# sd_tos_dip28.net
KiCad netlist of a schematic drawn in EAGLE
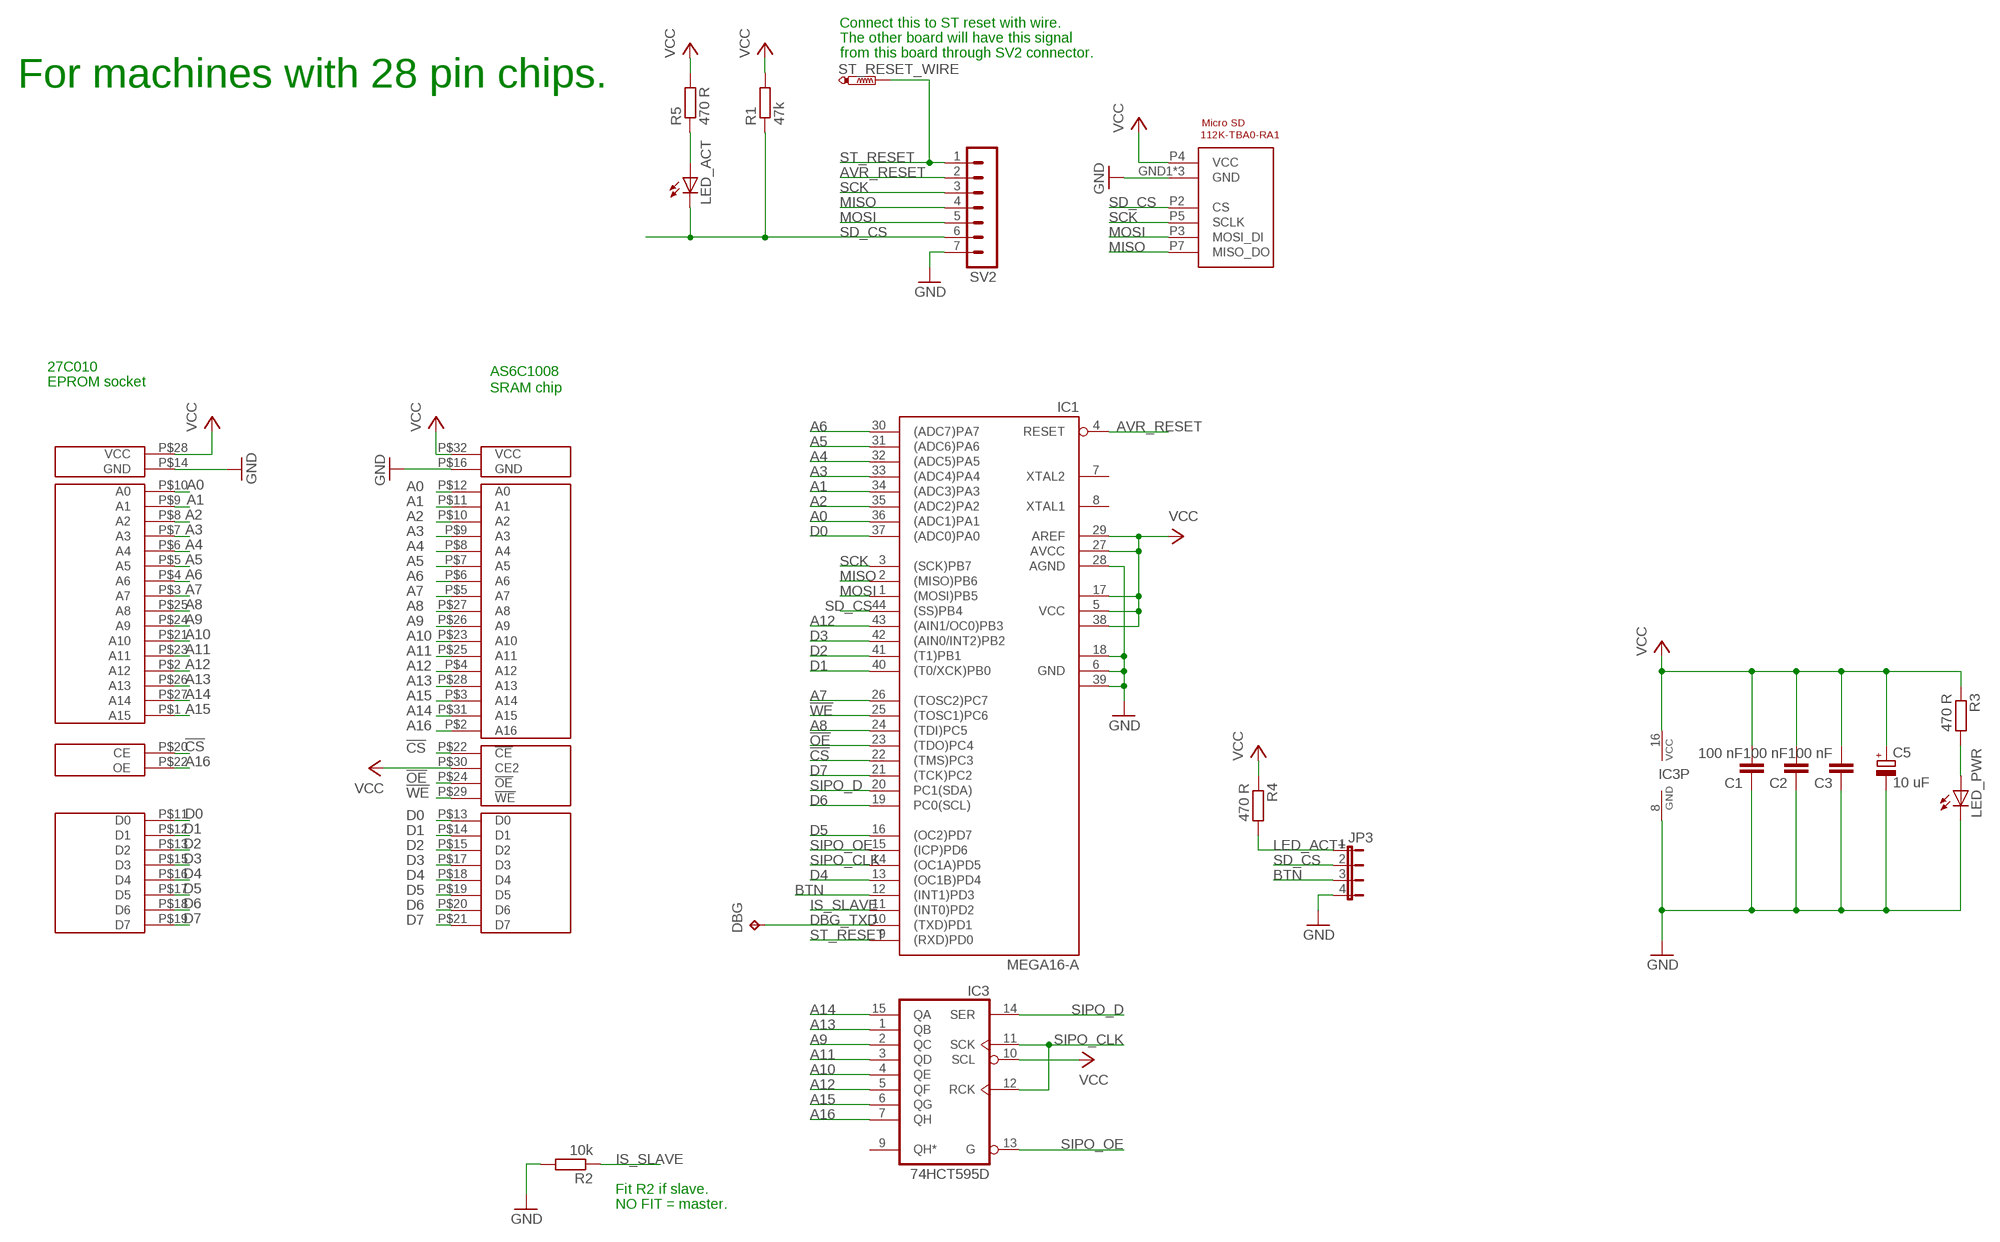
[diagram p0: schematic, sheet 1]

(export (version "E")
  (design (tool "Eeschema 10.0.6"))
  (components
    (comp (ref "C1")
      (value "100 nF")
      (footprint "eagle-import:C0603")
      (libsource (lib "eagle-import") (part "C-EUC0603"))
    )
    (comp (ref "C2")
      (value "100 nF")
      (footprint "eagle-import:C0603")
      (libsource (lib "eagle-import") (part "C-EUC0603"))
    )
    (comp (ref "C3")
      (value "100 nF")
      (footprint "eagle-import:C0603")
      (libsource (lib "eagle-import") (part "C-EUC0603"))
    )
    (comp (ref "C5")
      (value "10 uF")
      (footprint "eagle-import:SANYO-OSCON_SMD_B6")
      (libsource (lib "eagle-import") (part "CPOL-EUSANYO_SMD_B6"))
    )
    (comp (ref "DBG")
      (value "TPB1,27")
      (footprint "eagle-import:B1,27")
      (libsource (lib "eagle-import") (part "TPB1,27"))
    )
    (comp (ref "IC1")
      (value "MEGA16-A")
      (footprint "eagle-import:TQFP44")
      (libsource (lib "eagle-import") (part "MEGA16-A"))
    )
    (comp (ref "IC3")
      (value "74HCT595D")
      (footprint "eagle-import:SO16")
      (libsource (lib "eagle-import") (part "74595DHCT"))
    )
    (comp (ref "JP3")
      (value "JP4E")
      (footprint "eagle-import:JP4")
      (libsource (lib "eagle-import") (part "JP4E"))
    )
    (comp (ref "LED_ACT")
      (value "LEDCHIP-LED0805")
      (footprint "eagle-import:CHIP-LED0805")
      (libsource (lib "eagle-import") (part "LEDCHIP-LED0805"))
    )
    (comp (ref "LED_PWR")
      (value "LEDCHIP-LED0805")
      (footprint "eagle-import:CHIP-LED0805")
      (libsource (lib "eagle-import") (part "LEDCHIP-LED0805"))
    )
    (comp (ref "R1")
      (value "47k")
      (footprint "eagle-import:R0603")
      (libsource (lib "eagle-import") (part "R-EU_R0603"))
    )
    (comp (ref "R2")
      (value "10k")
      (footprint "eagle-import:R0603")
      (libsource (lib "eagle-import") (part "R-EU_R0603"))
    )
    (comp (ref "R3")
      (value "470 R")
      (footprint "eagle-import:R0603")
      (libsource (lib "eagle-import") (part "R-EU_R0603"))
    )
    (comp (ref "R4")
      (value "470 R")
      (footprint "eagle-import:R0603")
      (libsource (lib "eagle-import") (part "R-EU_R0603"))
    )
    (comp (ref "R5")
      (value "470 R")
      (footprint "eagle-import:R0603")
      (libsource (lib "eagle-import") (part "R-EU_R0603"))
    )
    (comp (ref "ST_RESET_WIRE")
      (value "PTR1PAD1-13")
      (footprint "eagle-import:P1-13")
      (libsource (lib "eagle-import") (part "PTR1PAD1-13"))
    )
    (comp (ref "SV2")
      (value "MA07-1")
      (footprint "eagle-import:MA07-1")
      (libsource (lib "eagle-import") (part "MA07-1"))
    )
    (comp (ref "U$1")
      (value "27C256BOTTOM_ONLY")
      (footprint "eagle-import:DIP28_BOTTOM_ONLY")
      (libsource (lib "eagle-import") (part "27C256BOTTOM_ONLY"))
    )
    (comp (ref "U$2")
      (value "AS6C1008DIP32")
      (footprint "eagle-import:DIP32")
      (libsource (lib "eagle-import") (part "AS6C1008DIP32"))
    )
    (comp (ref "U$3")
      (value "MICRO_SD")
      (footprint "eagle-import:MICRO_SD")
      (libsource (lib "eagle-import") (part "MICRO_SD"))
    )
  )
  (nets
    (net (code "1") (name "/A0") (class "Default")
      (node (ref "IC1") (pin "36") (pinfunction "(ADC1)PA1_36") (pintype "bidirectional"))
      (node (ref "U$1") (pin "P$10") (pinfunction "A0_P$10") (pintype "bidirectional"))
      (node (ref "U$2") (pin "P$12") (pinfunction "A0_P$12") (pintype "bidirectional"))
    )
    (net (code "2") (name "/A1") (class "Default")
      (node (ref "IC1") (pin "34") (pinfunction "(ADC3)PA3_34") (pintype "bidirectional"))
      (node (ref "U$1") (pin "P$9") (pinfunction "A1_P$9") (pintype "bidirectional"))
      (node (ref "U$2") (pin "P$11") (pinfunction "A1_P$11") (pintype "bidirectional"))
    )
    (net (code "3") (name "/A2") (class "Default")
      (node (ref "IC1") (pin "35") (pinfunction "(ADC2)PA2_35") (pintype "bidirectional"))
      (node (ref "U$1") (pin "P$8") (pinfunction "A2_P$8") (pintype "bidirectional"))
      (node (ref "U$2") (pin "P$10") (pinfunction "A2_P$10") (pintype "bidirectional"))
    )
    (net (code "4") (name "/A3") (class "Default")
      (node (ref "IC1") (pin "33") (pinfunction "(ADC4)PA4_33") (pintype "bidirectional"))
      (node (ref "U$1") (pin "P$7") (pinfunction "A3_P$7") (pintype "bidirectional"))
      (node (ref "U$2") (pin "P$9") (pinfunction "A3_P$9") (pintype "bidirectional"))
    )
    (net (code "5") (name "/A4") (class "Default")
      (node (ref "IC1") (pin "32") (pinfunction "(ADC5)PA5_32") (pintype "bidirectional"))
      (node (ref "U$1") (pin "P$6") (pinfunction "A4_P$6") (pintype "bidirectional"))
      (node (ref "U$2") (pin "P$8") (pinfunction "A4_P$8") (pintype "bidirectional"))
    )
    (net (code "6") (name "/A5") (class "Default")
      (node (ref "IC1") (pin "31") (pinfunction "(ADC6)PA6_31") (pintype "bidirectional"))
      (node (ref "U$1") (pin "P$5") (pinfunction "A5_P$5") (pintype "bidirectional"))
      (node (ref "U$2") (pin "P$7") (pinfunction "A5_P$7") (pintype "bidirectional"))
    )
    (net (code "7") (name "/A6") (class "Default")
      (node (ref "IC1") (pin "30") (pinfunction "(ADC7)PA7_30") (pintype "bidirectional"))
      (node (ref "U$1") (pin "P$4") (pinfunction "A6_P$4") (pintype "bidirectional"))
      (node (ref "U$2") (pin "P$6") (pinfunction "A6_P$6") (pintype "bidirectional"))
    )
    (net (code "8") (name "/A7") (class "Default")
      (node (ref "IC1") (pin "26") (pinfunction "(TOSC2)PC7_26") (pintype "bidirectional"))
      (node (ref "U$1") (pin "P$3") (pinfunction "A7_P$3") (pintype "bidirectional"))
      (node (ref "U$2") (pin "P$5") (pinfunction "A7_P$5") (pintype "bidirectional"))
    )
    (net (code "9") (name "/A8") (class "Default")
      (node (ref "IC1") (pin "24") (pinfunction "(TDI)PC5_24") (pintype "bidirectional"))
      (node (ref "U$1") (pin "P$25") (pinfunction "A8_P$25") (pintype "bidirectional"))
      (node (ref "U$2") (pin "P$27") (pinfunction "A8_P$27") (pintype "bidirectional"))
    )
    (net (code "10") (name "/A9") (class "Default")
      (node (ref "IC3") (pin "2") (pinfunction "QC_2") (pintype "tri_state"))
      (node (ref "U$1") (pin "P$24") (pinfunction "A9_P$24") (pintype "bidirectional"))
      (node (ref "U$2") (pin "P$26") (pinfunction "A9_P$26") (pintype "bidirectional"))
    )
    (net (code "11") (name "/A10") (class "Default")
      (node (ref "IC3") (pin "4") (pinfunction "QE_4") (pintype "tri_state"))
      (node (ref "U$1") (pin "P$21") (pinfunction "A10_P$21") (pintype "bidirectional"))
      (node (ref "U$2") (pin "P$23") (pinfunction "A10_P$23") (pintype "bidirectional"))
    )
    (net (code "12") (name "/A11") (class "Default")
      (node (ref "IC3") (pin "3") (pinfunction "QD_3") (pintype "tri_state"))
      (node (ref "U$1") (pin "P$23") (pinfunction "A11_P$23") (pintype "bidirectional"))
      (node (ref "U$2") (pin "P$25") (pinfunction "A11_P$25") (pintype "bidirectional"))
    )
    (net (code "13") (name "/A12") (class "Default")
      (node (ref "IC1") (pin "43") (pinfunction "(AIN1/OC0)PB3_43") (pintype "bidirectional"))
      (node (ref "IC3") (pin "5") (pinfunction "QF_5") (pintype "tri_state"))
      (node (ref "U$1") (pin "P$2") (pinfunction "A12_P$2") (pintype "bidirectional"))
      (node (ref "U$2") (pin "P$4") (pinfunction "A12_P$4") (pintype "bidirectional"))
    )
    (net (code "14") (name "/A13") (class "Default")
      (node (ref "IC3") (pin "1") (pinfunction "QB_1") (pintype "tri_state"))
      (node (ref "U$1") (pin "P$26") (pinfunction "A13_P$26") (pintype "bidirectional"))
      (node (ref "U$2") (pin "P$28") (pinfunction "A13_P$28") (pintype "bidirectional"))
    )
    (net (code "15") (name "/A14") (class "Default")
      (node (ref "IC3") (pin "15") (pinfunction "QA_15") (pintype "tri_state"))
      (node (ref "U$1") (pin "P$27") (pinfunction "A14_P$27") (pintype "bidirectional"))
      (node (ref "U$2") (pin "P$31") (pinfunction "A15_P$31") (pintype "bidirectional"))
    )
    (net (code "16") (name "/A15") (class "Default")
      (node (ref "IC3") (pin "6") (pinfunction "QG_6") (pintype "tri_state"))
      (node (ref "U$1") (pin "P$1") (pinfunction "A15_P$1") (pintype "bidirectional"))
      (node (ref "U$2") (pin "P$3") (pinfunction "A14_P$3") (pintype "bidirectional"))
    )
    (net (code "17") (name "/A16") (class "Default")
      (node (ref "IC3") (pin "7") (pinfunction "QH_7") (pintype "tri_state"))
      (node (ref "U$1") (pin "P$22") (pinfunction "OE_P$22") (pintype "bidirectional"))
      (node (ref "U$2") (pin "P$2") (pinfunction "A16_P$2") (pintype "bidirectional"))
    )
    (net (code "18") (name "/AVR_RESET") (class "Default")
      (node (ref "IC1") (pin "4") (pinfunction "RESET_4") (pintype "input"))
      (node (ref "SV2") (pin "2") (pinfunction "2_2") (pintype "passive"))
    )
    (net (code "19") (name "/BTN") (class "Default")
      (node (ref "IC1") (pin "12") (pinfunction "(INT1)PD3_12") (pintype "bidirectional"))
      (node (ref "JP3") (pin "3") (pinfunction "3_3") (pintype "passive"))
    )
    (net (code "20") (name "/D0") (class "Default")
      (node (ref "IC1") (pin "37") (pinfunction "(ADC0)PA0_37") (pintype "bidirectional"))
      (node (ref "U$1") (pin "P$11") (pinfunction "D0_P$11") (pintype "bidirectional"))
      (node (ref "U$2") (pin "P$13") (pinfunction "D0_P$13") (pintype "bidirectional"))
    )
    (net (code "21") (name "/D1") (class "Default")
      (node (ref "IC1") (pin "40") (pinfunction "(T0/XCK)PB0_40") (pintype "bidirectional"))
      (node (ref "U$1") (pin "P$12") (pinfunction "D1_P$12") (pintype "bidirectional"))
      (node (ref "U$2") (pin "P$14") (pinfunction "D1_P$14") (pintype "bidirectional"))
    )
    (net (code "22") (name "/D2") (class "Default")
      (node (ref "IC1") (pin "41") (pinfunction "(T1)PB1_41") (pintype "bidirectional"))
      (node (ref "U$1") (pin "P$13") (pinfunction "D2_P$13") (pintype "bidirectional"))
      (node (ref "U$2") (pin "P$15") (pinfunction "D2_P$15") (pintype "bidirectional"))
    )
    (net (code "23") (name "/D3") (class "Default")
      (node (ref "IC1") (pin "42") (pinfunction "(AIN0/INT2)PB2_42") (pintype "bidirectional"))
      (node (ref "U$1") (pin "P$15") (pinfunction "D3_P$15") (pintype "bidirectional"))
      (node (ref "U$2") (pin "P$17") (pinfunction "D3_P$17") (pintype "bidirectional"))
    )
    (net (code "24") (name "/D4") (class "Default")
      (node (ref "IC1") (pin "13") (pinfunction "(OC1B)PD4_13") (pintype "bidirectional"))
      (node (ref "U$1") (pin "P$16") (pinfunction "D4_P$16") (pintype "bidirectional"))
      (node (ref "U$2") (pin "P$18") (pinfunction "D4_P$18") (pintype "bidirectional"))
    )
    (net (code "25") (name "/D5") (class "Default")
      (node (ref "IC1") (pin "16") (pinfunction "(OC2)PD7_16") (pintype "bidirectional"))
      (node (ref "U$1") (pin "P$17") (pinfunction "D5_P$17") (pintype "bidirectional"))
      (node (ref "U$2") (pin "P$19") (pinfunction "D5_P$19") (pintype "bidirectional"))
    )
    (net (code "26") (name "/D6") (class "Default")
      (node (ref "IC1") (pin "19") (pinfunction "PC0(SCL)_19") (pintype "bidirectional"))
      (node (ref "U$1") (pin "P$18") (pinfunction "D6_P$18") (pintype "bidirectional"))
      (node (ref "U$2") (pin "P$20") (pinfunction "D6_P$20") (pintype "bidirectional"))
    )
    (net (code "27") (name "/D7") (class "Default")
      (node (ref "IC1") (pin "21") (pinfunction "(TCK)PC2_21") (pintype "bidirectional"))
      (node (ref "U$1") (pin "P$19") (pinfunction "D7_P$19") (pintype "bidirectional"))
      (node (ref "U$2") (pin "P$21") (pinfunction "D7_P$21") (pintype "bidirectional"))
    )
    (net (code "28") (name "/DBG_TXD") (class "Default")
      (node (ref "DBG") (pin "TP") (pinfunction "TP_TP") (pintype "input"))
      (node (ref "IC1") (pin "10") (pinfunction "(TXD)PD1_10") (pintype "bidirectional"))
    )
    (net (code "29") (name "/IS_SLAVE") (class "Default")
      (node (ref "IC1") (pin "11") (pinfunction "(INT0)PD2_11") (pintype "bidirectional"))
      (node (ref "R2") (pin "1") (pinfunction "1_1") (pintype "passive"))
    )
    (net (code "30") (name "/LED_ACT+") (class "Default")
      (node (ref "JP3") (pin "1") (pinfunction "1_1") (pintype "passive"))
      (node (ref "R4") (pin "2") (pinfunction "2_2") (pintype "passive"))
    )
    (net (code "31") (name "/MISO") (class "Default")
      (node (ref "IC1") (pin "2") (pinfunction "(MISO)PB6_2") (pintype "bidirectional"))
      (node (ref "SV2") (pin "4") (pinfunction "4_4") (pintype "passive"))
      (node (ref "U$3") (pin "P7") (pinfunction "MISO_DO_P7") (pintype "output"))
    )
    (net (code "32") (name "/MOSI") (class "Default")
      (node (ref "IC1") (pin "1") (pinfunction "(MOSI)PB5_1") (pintype "bidirectional"))
      (node (ref "SV2") (pin "5") (pinfunction "5_5") (pintype "passive"))
      (node (ref "U$3") (pin "P3") (pinfunction "MOSI_DI_P3") (pintype "input"))
    )
    (net (code "33") (name "/SCK") (class "Default")
      (node (ref "IC1") (pin "3") (pinfunction "(SCK)PB7_3") (pintype "bidirectional"))
      (node (ref "SV2") (pin "3") (pinfunction "3_3") (pintype "passive"))
      (node (ref "U$3") (pin "P5") (pinfunction "SCLK_P5") (pintype "input"))
    )
    (net (code "34") (name "/SD_CS") (class "Default")
      (node (ref "IC1") (pin "44") (pinfunction "(SS)PB4_44") (pintype "bidirectional"))
      (node (ref "JP3") (pin "2") (pinfunction "2_2") (pintype "passive"))
      (node (ref "LED_ACT") (pin "C") (pinfunction "C_C") (pintype "passive"))
      (node (ref "R1") (pin "1") (pinfunction "1_1") (pintype "passive"))
      (node (ref "SV2") (pin "6") (pinfunction "6_6") (pintype "passive"))
      (node (ref "U$3") (pin "P2") (pinfunction "CS_P2") (pintype "input"))
    )
    (net (code "35") (name "/SIPO_CLK") (class "Default")
      (node (ref "IC1") (pin "14") (pinfunction "(OC1A)PD5_14") (pintype "bidirectional"))
      (node (ref "IC3") (pin "11") (pinfunction "SCK_11") (pintype "input"))
      (node (ref "IC3") (pin "12") (pinfunction "RCK_12") (pintype "input"))
    )
    (net (code "36") (name "/SIPO_D") (class "Default")
      (node (ref "IC1") (pin "20") (pinfunction "PC1(SDA)_20") (pintype "bidirectional"))
      (node (ref "IC3") (pin "14") (pinfunction "SER_14") (pintype "input"))
    )
    (net (code "37") (name "/SIPO_OE") (class "Default")
      (node (ref "IC1") (pin "15") (pinfunction "(ICP)PD6_15") (pintype "bidirectional"))
      (node (ref "IC3") (pin "13") (pinfunction "G_13") (pintype "input"))
    )
    (net (code "38") (name "/ST_RESET") (class "Default")
      (node (ref "IC1") (pin "9") (pinfunction "(RXD)PD0_9") (pintype "bidirectional"))
      (node (ref "ST_RESET_WIRE") (pin "TP") (pinfunction "TP_TP") (pintype "input"))
      (node (ref "SV2") (pin "1") (pinfunction "1_1") (pintype "passive"))
    )
    (net (code "39") (name "/~{CS}") (class "Default")
      (node (ref "IC1") (pin "22") (pinfunction "(TMS)PC3_22") (pintype "bidirectional"))
      (node (ref "U$1") (pin "P$20") (pinfunction "CE_P$20") (pintype "bidirectional"))
      (node (ref "U$2") (pin "P$22") (pinfunction "~{CE}_P$22") (pintype "bidirectional"))
    )
    (net (code "40") (name "/~{OE}") (class "Default")
      (node (ref "IC1") (pin "23") (pinfunction "(TDO)PC4_23") (pintype "bidirectional"))
      (node (ref "U$2") (pin "P$24") (pinfunction "~{OE}_P$24") (pintype "bidirectional"))
    )
    (net (code "41") (name "/~{WE}") (class "Default")
      (node (ref "IC1") (pin "25") (pinfunction "(TOSC1)PC6_25") (pintype "bidirectional"))
      (node (ref "U$2") (pin "P$29") (pinfunction "~{WE}_P$29") (pintype "bidirectional"))
    )
    (net (code "42") (name "GND") (class "Default")
      (node (ref "C1") (pin "1") (pinfunction "1_1") (pintype "passive"))
      (node (ref "C2") (pin "1") (pinfunction "1_1") (pintype "passive"))
      (node (ref "C3") (pin "1") (pinfunction "1_1") (pintype "passive"))
      (node (ref "C5") (pin "-") (pinfunction "-_-") (pintype "passive"))
      (node (ref "IC1") (pin "18") (pinfunction "GND1_18") (pintype "power_in"))
      (node (ref "IC1") (pin "28") (pinfunction "AGND_28") (pintype "power_in"))
      (node (ref "IC1") (pin "39") (pinfunction "GND2_39") (pintype "power_in"))
      (node (ref "IC1") (pin "6") (pinfunction "GND_6") (pintype "power_in"))
      (node (ref "IC3") (pin "8") (pinfunction "GND_8") (pintype "power_in"))
      (node (ref "JP3") (pin "4") (pinfunction "4_4") (pintype "passive"))
      (node (ref "LED_PWR") (pin "C") (pinfunction "C_C") (pintype "passive"))
      (node (ref "R2") (pin "2") (pinfunction "2_2") (pintype "passive"))
      (node (ref "SV2") (pin "7") (pinfunction "7_7") (pintype "passive"))
      (node (ref "U$1") (pin "P$14") (pinfunction "GND_P$14") (pintype "bidirectional"))
      (node (ref "U$2") (pin "P$16") (pinfunction "GND_P$16") (pintype "bidirectional"))
      (node (ref "U$3") (pin "GND1") (pinfunction "GND_GND1") (pintype "power_in"))
      (node (ref "U$3") (pin "GND2") (pinfunction "GND_GND2") (pintype "power_in"))
      (node (ref "U$3") (pin "P6") (pinfunction "GND_P6") (pintype "power_in"))
    )
    (net (code "43") (name "Net-(LED_ACT-PadA)") (class "Default")
      (node (ref "LED_ACT") (pin "A") (pinfunction "A_A") (pintype "passive"))
      (node (ref "R5") (pin "1") (pinfunction "1_1") (pintype "passive"))
    )
    (net (code "44") (name "Net-(LED_PWR-PadA)") (class "Default")
      (node (ref "LED_PWR") (pin "A") (pinfunction "A_A") (pintype "passive"))
      (node (ref "R3") (pin "2") (pinfunction "2_2") (pintype "passive"))
    )
    (net (code "45") (name "VCC") (class "Default")
      (node (ref "C1") (pin "2") (pinfunction "2_2") (pintype "passive"))
      (node (ref "C2") (pin "2") (pinfunction "2_2") (pintype "passive"))
      (node (ref "C3") (pin "2") (pinfunction "2_2") (pintype "passive"))
      (node (ref "C5") (pin "+") (pinfunction "+_+") (pintype "passive"))
      (node (ref "IC1") (pin "17") (pinfunction "VCC1_17") (pintype "power_in"))
      (node (ref "IC1") (pin "27") (pinfunction "AVCC_27") (pintype "power_in"))
      (node (ref "IC1") (pin "29") (pinfunction "AREF_29") (pintype "power_in"))
      (node (ref "IC1") (pin "38") (pinfunction "VCC2_38") (pintype "power_in"))
      (node (ref "IC1") (pin "5") (pinfunction "VCC_5") (pintype "power_in"))
      (node (ref "IC3") (pin "10") (pinfunction "SCL_10") (pintype "input"))
      (node (ref "IC3") (pin "16") (pinfunction "VCC_16") (pintype "power_in"))
      (node (ref "R1") (pin "2") (pinfunction "2_2") (pintype "passive"))
      (node (ref "R3") (pin "1") (pinfunction "1_1") (pintype "passive"))
      (node (ref "R4") (pin "1") (pinfunction "1_1") (pintype "passive"))
      (node (ref "R5") (pin "2") (pinfunction "2_2") (pintype "passive"))
      (node (ref "U$1") (pin "P$28") (pinfunction "VCC_P$28") (pintype "bidirectional"))
      (node (ref "U$2") (pin "P$30") (pinfunction "CE2_P$30") (pintype "bidirectional"))
      (node (ref "U$2") (pin "P$32") (pinfunction "VCC_P$32") (pintype "bidirectional"))
      (node (ref "U$3") (pin "P4") (pinfunction "VCC_P4") (pintype "power_in"))
    )
    (net (code "46") (name "unconnected-(IC1-XTAL1-Pad8)") (class "Default")
      (node (ref "IC1") (pin "8") (pinfunction "XTAL1_8") (pintype "bidirectional"))
    )
    (net (code "47") (name "unconnected-(IC1-XTAL2-Pad7)") (class "Default")
      (node (ref "IC1") (pin "7") (pinfunction "XTAL2_7") (pintype "bidirectional"))
    )
    (net (code "48") (name "unconnected-(IC3A-QH*-Pad9)") (class "Default")
      (node (ref "IC3") (pin "9") (pinfunction "QH*_9") (pintype "tri_state"))
    )
  )
)
